# tiny13_charlie4_50mm_coincell_optical_di.net
KiCad netlist of a schematic drawn in EAGLE
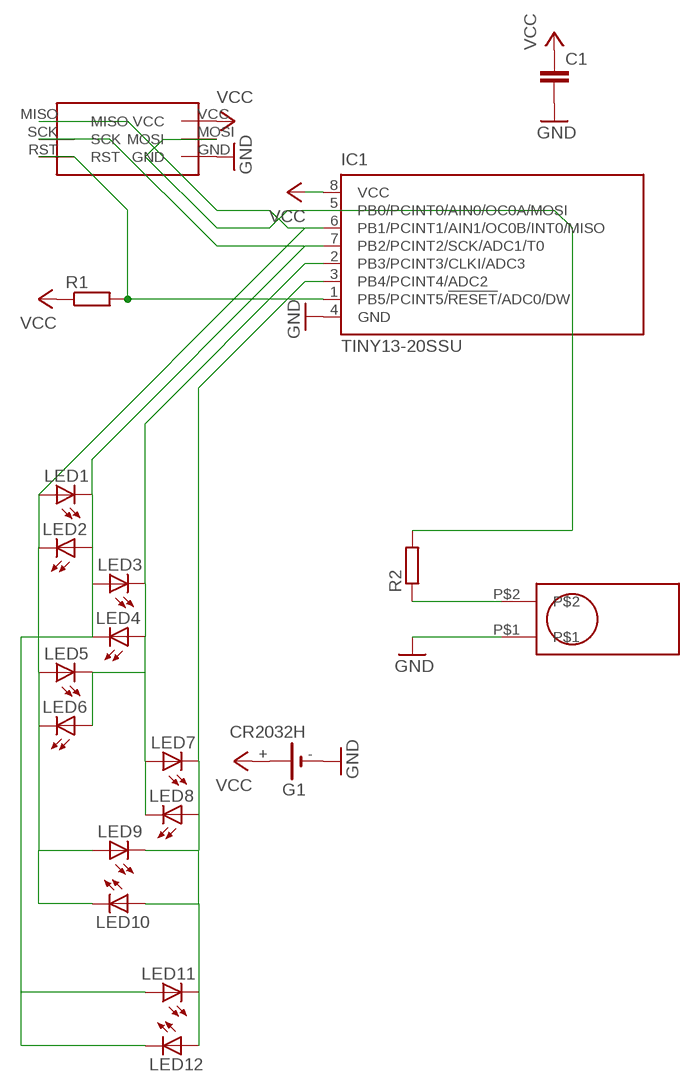
[diagram p0: schematic, sheet 1]

(export (version "E")
  (design (tool "Eeschema 10.0.6"))
  (components
    (comp (ref "C1")
      (value "C-EU025-025X050")
      (footprint "eagle-import:C025-025X050")
      (libsource (lib "eagle-import") (part "C-EU025-025X050"))
    )
    (comp (ref "G1")
      (value "CR2032H")
      (footprint "eagle-import:CR2032H")
      (libsource (lib "eagle-import") (part "CR2032H"))
    )
    (comp (ref "IC1")
      (value "TINY13-20SSU")
      (footprint "eagle-import:8S1")
      (fields (field (name "MPN") "ATTINY13-20SSU"))
      (libsource (lib "eagle-import") (part "TINY13SSU-20"))
    )
    (comp (ref "LED1")
      (value "LED3MM")
      (footprint "eagle-import:LED3MM")
      (libsource (lib "eagle-import") (part "LED3MM"))
    )
    (comp (ref "LED2")
      (value "LED3MM")
      (footprint "eagle-import:LED3MM")
      (libsource (lib "eagle-import") (part "LED3MM"))
    )
    (comp (ref "LED3")
      (value "LED3MM")
      (footprint "eagle-import:LED3MM")
      (libsource (lib "eagle-import") (part "LED3MM"))
    )
    (comp (ref "LED4")
      (value "LED3MM")
      (footprint "eagle-import:LED3MM")
      (libsource (lib "eagle-import") (part "LED3MM"))
    )
    (comp (ref "LED5")
      (value "LED3MM")
      (footprint "eagle-import:LED3MM")
      (libsource (lib "eagle-import") (part "LED3MM"))
    )
    (comp (ref "LED6")
      (value "LED3MM")
      (footprint "eagle-import:LED3MM")
      (libsource (lib "eagle-import") (part "LED3MM"))
    )
    (comp (ref "LED7")
      (value "LED3MM")
      (footprint "eagle-import:LED3MM")
      (libsource (lib "eagle-import") (part "LED3MM"))
    )
    (comp (ref "LED8")
      (value "LED3MM")
      (footprint "eagle-import:LED3MM")
      (libsource (lib "eagle-import") (part "LED3MM"))
    )
    (comp (ref "LED9")
      (value "LED3MM")
      (footprint "eagle-import:LED3MM")
      (libsource (lib "eagle-import") (part "LED3MM"))
    )
    (comp (ref "LED10")
      (value "LED3MM")
      (footprint "eagle-import:LED3MM")
      (libsource (lib "eagle-import") (part "LED3MM"))
    )
    (comp (ref "LED11")
      (value "LED3MM")
      (footprint "eagle-import:LED3MM")
      (libsource (lib "eagle-import") (part "LED3MM"))
    )
    (comp (ref "LED12")
      (value "LED3MM")
      (footprint "eagle-import:LED3MM")
      (libsource (lib "eagle-import") (part "LED3MM"))
    )
    (comp (ref "R1")
      (value "R-EU_0204/5")
      (footprint "eagle-import:0204_5")
      (libsource (lib "eagle-import") (part "R-EU_0204/5"))
    )
    (comp (ref "R2")
      (value "R-EU_0204/5")
      (footprint "eagle-import:0204_5")
      (libsource (lib "eagle-import") (part "R-EU_0204/5"))
    )
    (comp (ref "U$1")
      (value "TILT_SWITCH_MECHANICAL")
      (footprint "eagle-import:TILT_SWITCH_MECHANICAL")
      (libsource (lib "eagle-import") (part "TILT_SWITCH_MECHANICAL"))
    )
    (comp (ref "U$2")
      (value "AVR_ISP_6_PIN_1X6_SMT_CONTACT_BIG")
      (footprint "eagle-import:CONTACT_ISP_PROGRAMMER_1X6_ATMEL")
      (libsource (lib "eagle-import") (part "AVR_ISP_6_PIN_1X6_SMT_CONTACT_BIG"))
    )
  )
  (nets
    (net (code "1") (name "GND") (class "Default")
      (node (ref "C1") (pin "2") (pinfunction "2_2") (pintype "passive"))
      (node (ref "G1") (pin "-") (pinfunction "-_-") (pintype "passive"))
      (node (ref "IC1") (pin "4") (pinfunction "GND_4") (pintype "power_in"))
      (node (ref "U$1") (pin "P$1") (pinfunction "P$1_P$1") (pintype "bidirectional"))
      (node (ref "U$2") (pin "GND") (pinfunction "GND_GND") (pintype "bidirectional"))
    )
    (net (code "2") (name "Net-(IC1-PB0{slash}PCINT0{slash}AIN0{slash}OC0A{slash}MOSI)") (class "Default")
      (node (ref "IC1") (pin "5") (pinfunction "PB0/PCINT0/AIN0/OC0A/MOSI_5") (pintype "bidirectional"))
      (node (ref "R2") (pin "2") (pinfunction "2_2") (pintype "passive"))
      (node (ref "U$2") (pin "MOSI") (pinfunction "MOSI_MOSI") (pintype "bidirectional"))
    )
    (net (code "3") (name "Net-(IC1-PB1{slash}PCINT1{slash}AIN1{slash}OC0B{slash}INT0{slash}MISO)") (class "Default")
      (node (ref "IC1") (pin "6") (pinfunction "PB1/PCINT1/AIN1/OC0B/INT0/MISO_6") (pintype "bidirectional"))
      (node (ref "LED1") (pin "A") (pinfunction "A_A") (pintype "passive"))
      (node (ref "LED10") (pin "K") (pinfunction "C_K") (pintype "passive"))
      (node (ref "LED2") (pin "K") (pinfunction "C_K") (pintype "passive"))
      (node (ref "LED5") (pin "A") (pinfunction "A_A") (pintype "passive"))
      (node (ref "LED6") (pin "K") (pinfunction "C_K") (pintype "passive"))
      (node (ref "LED9") (pin "A") (pinfunction "A_A") (pintype "passive"))
      (node (ref "U$2") (pin "MISO") (pinfunction "MISO_MISO") (pintype "bidirectional"))
    )
    (net (code "4") (name "Net-(IC1-PB2{slash}PCINT2{slash}SCK{slash}ADC1{slash}T0)") (class "Default")
      (node (ref "IC1") (pin "7") (pinfunction "PB2/PCINT2/SCK/ADC1/T0_7") (pintype "bidirectional"))
      (node (ref "LED1") (pin "K") (pinfunction "C_K") (pintype "passive"))
      (node (ref "LED11") (pin "A") (pinfunction "A_A") (pintype "passive"))
      (node (ref "LED12") (pin "K") (pinfunction "C_K") (pintype "passive"))
      (node (ref "LED2") (pin "A") (pinfunction "A_A") (pintype "passive"))
      (node (ref "LED3") (pin "A") (pinfunction "A_A") (pintype "passive"))
      (node (ref "LED4") (pin "K") (pinfunction "C_K") (pintype "passive"))
      (node (ref "U$2") (pin "SCK") (pinfunction "SCK_SCK") (pintype "bidirectional"))
    )
    (net (code "5") (name "Net-(IC1-PB3{slash}PCINT3{slash}CLKI{slash}ADC3)") (class "Default")
      (node (ref "IC1") (pin "2") (pinfunction "PB3/PCINT3/CLKI/ADC3_2") (pintype "bidirectional"))
      (node (ref "LED3") (pin "K") (pinfunction "C_K") (pintype "passive"))
      (node (ref "LED4") (pin "A") (pinfunction "A_A") (pintype "passive"))
      (node (ref "LED5") (pin "K") (pinfunction "C_K") (pintype "passive"))
      (node (ref "LED6") (pin "A") (pinfunction "A_A") (pintype "passive"))
      (node (ref "LED7") (pin "A") (pinfunction "A_A") (pintype "passive"))
      (node (ref "LED8") (pin "K") (pinfunction "C_K") (pintype "passive"))
    )
    (net (code "6") (name "Net-(IC1-PB4{slash}PCINT4{slash}ADC2)") (class "Default")
      (node (ref "IC1") (pin "3") (pinfunction "PB4/PCINT4/ADC2_3") (pintype "bidirectional"))
      (node (ref "LED10") (pin "A") (pinfunction "A_A") (pintype "passive"))
      (node (ref "LED11") (pin "K") (pinfunction "C_K") (pintype "passive"))
      (node (ref "LED12") (pin "A") (pinfunction "A_A") (pintype "passive"))
      (node (ref "LED7") (pin "K") (pinfunction "C_K") (pintype "passive"))
      (node (ref "LED8") (pin "A") (pinfunction "A_A") (pintype "passive"))
      (node (ref "LED9") (pin "K") (pinfunction "C_K") (pintype "passive"))
    )
    (net (code "7") (name "Net-(IC1-PB5{slash}PCINT5{slash}~{RESET}{slash}ADC0{slash}DW)") (class "Default")
      (node (ref "IC1") (pin "1") (pinfunction "PB5/PCINT5/~{RESET}/ADC0/DW_1") (pintype "bidirectional"))
      (node (ref "R1") (pin "2") (pinfunction "2_2") (pintype "passive"))
      (node (ref "U$2") (pin "RST") (pinfunction "RST_RST") (pintype "bidirectional"))
    )
    (net (code "8") (name "Net-(R2-Pad1)") (class "Default")
      (node (ref "R2") (pin "1") (pinfunction "1_1") (pintype "passive"))
      (node (ref "U$1") (pin "P$2") (pinfunction "P$2_P$2") (pintype "bidirectional"))
    )
    (net (code "9") (name "VCC") (class "Default")
      (node (ref "C1") (pin "1") (pinfunction "1_1") (pintype "passive"))
      (node (ref "G1") (pin "+") (pinfunction "+_+") (pintype "passive"))
      (node (ref "IC1") (pin "8") (pinfunction "VCC_8") (pintype "power_in"))
      (node (ref "R1") (pin "1") (pinfunction "1_1") (pintype "passive"))
      (node (ref "U$2") (pin "VCC") (pinfunction "VCC_VCC") (pintype "bidirectional"))
    )
    (net (code "10") (name "unconnected-(G1-+-Pad+@1)") (class "Default")
      (node (ref "G1") (pin "+@1") (pinfunction "+_+@1") (pintype "passive"))
    )
  )
)
